# Project_Custom_Segmented_Display_2025-12.net
KiCad netlist of a schematic drawn in EasyEDA Pro
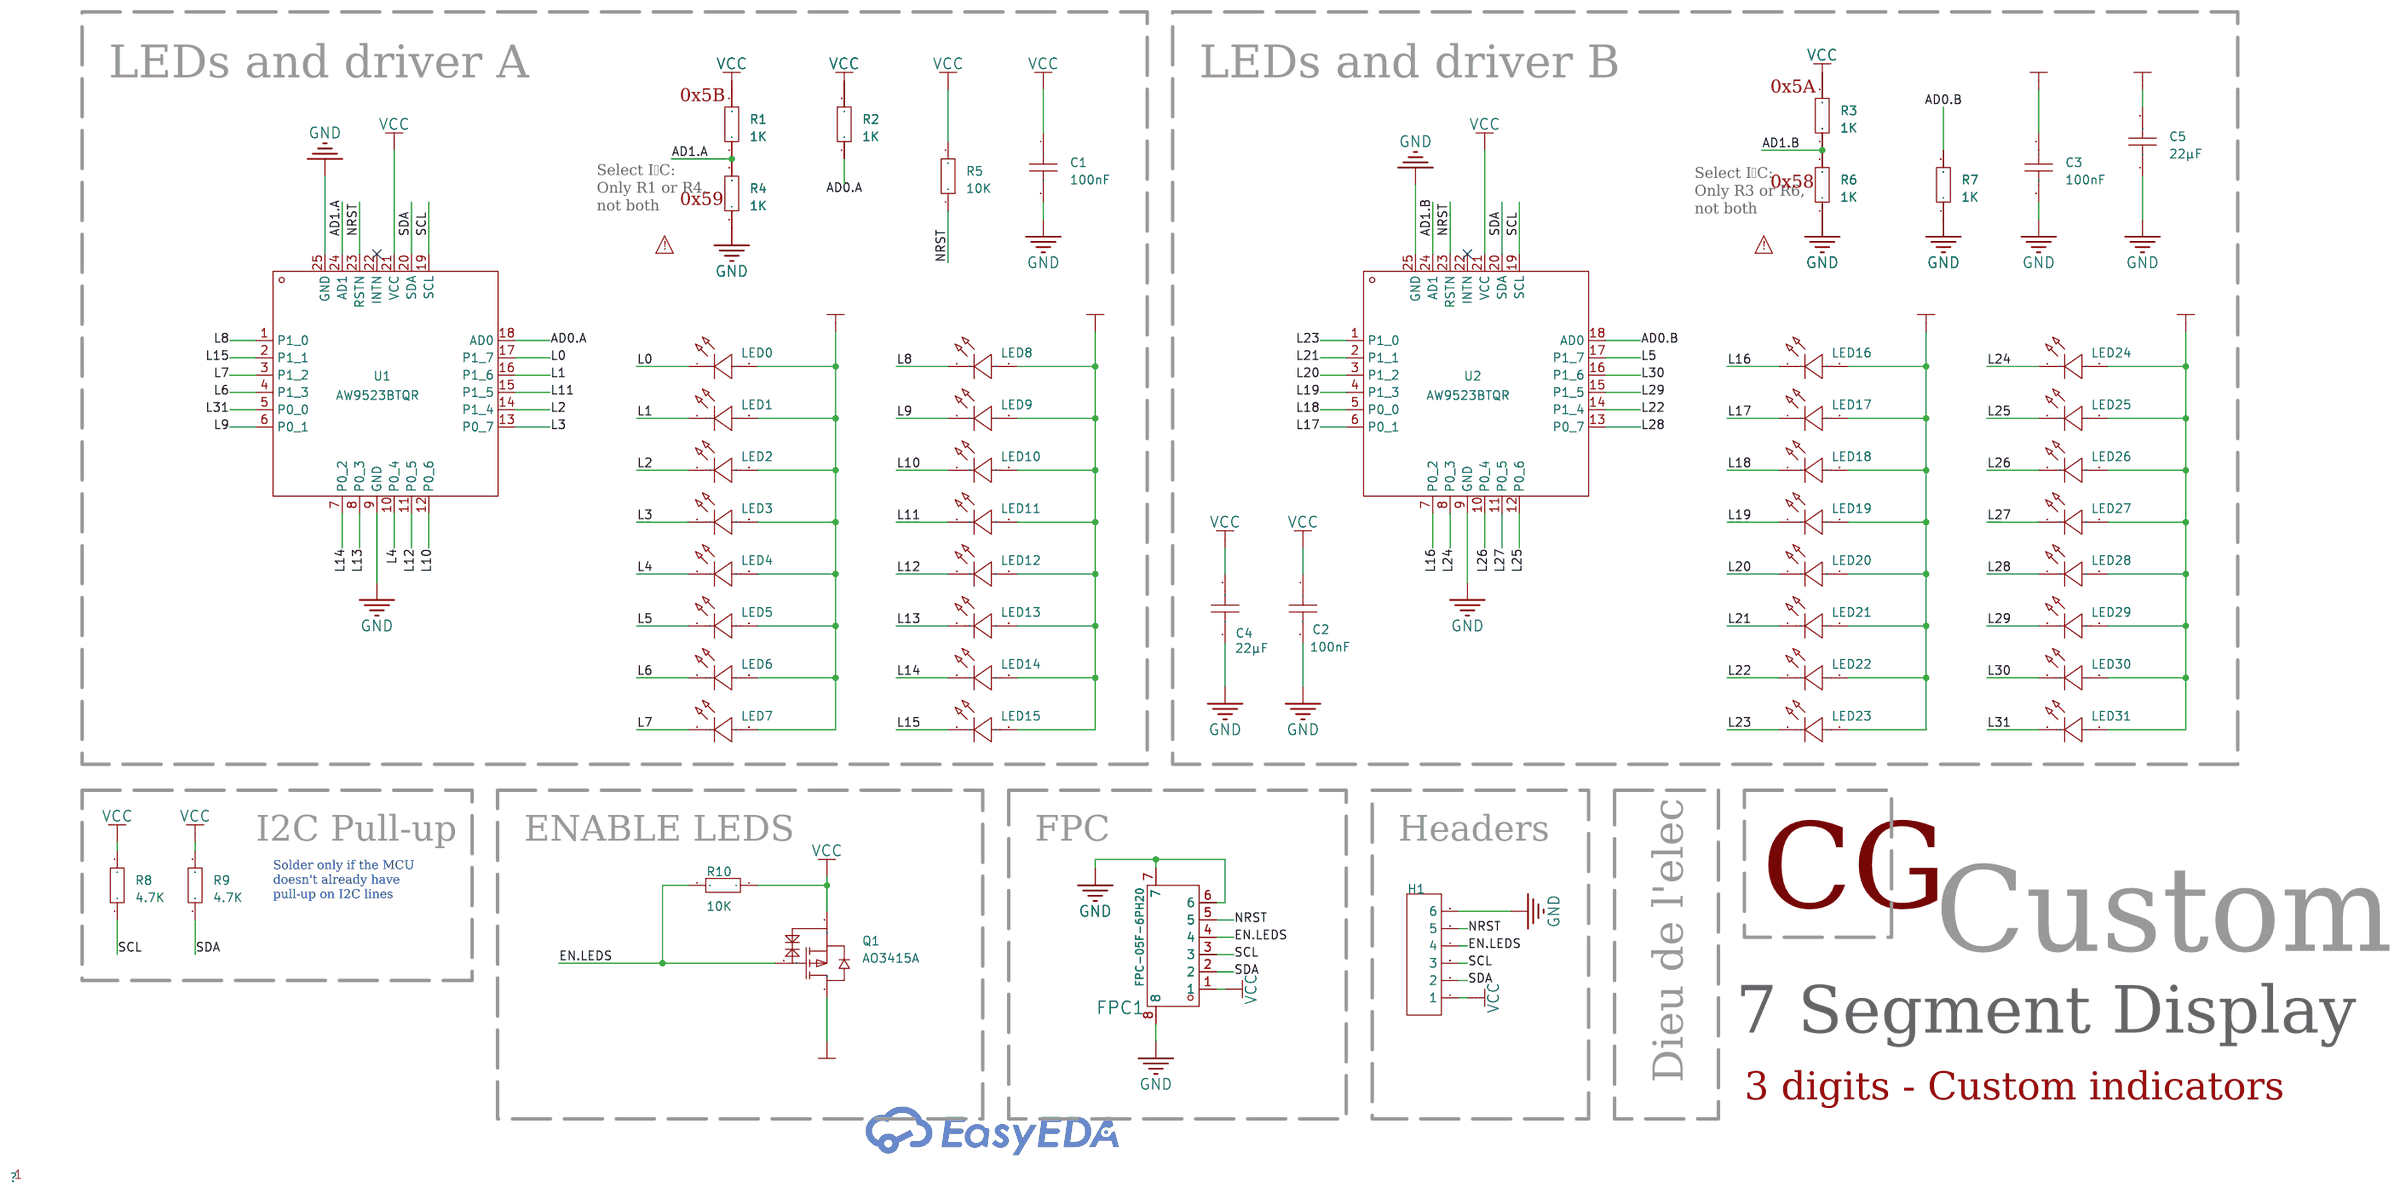
[diagram p0: schematic sheet]

(export (version "E")
  (design (tool "Eeschema 10.0.6"))
  (components
    (comp (ref "C1")
      (value "100nF")
      (footprint "easyedapro:C0805")
      (libsource (lib "easyedapro") (part "CAP"))
    )
    (comp (ref "C2")
      (value "100nF")
      (footprint "easyedapro:C0805")
      (libsource (lib "easyedapro") (part "CAP"))
    )
    (comp (ref "C3")
      (value "100nF")
      (footprint "easyedapro:C0805")
      (libsource (lib "easyedapro") (part "CAP"))
    )
    (comp (ref "C4")
      (value "22µF")
      (footprint "easyedapro:C0805")
      (libsource (lib "easyedapro") (part "CAP"))
    )
    (comp (ref "C5")
      (value "22µF")
      (footprint "easyedapro:C0805")
      (libsource (lib "easyedapro") (part "CAP"))
    )
    (comp (ref "FPC1")
      (value "FPC-05F-6PH20")
      (footprint "easyedapro:FPC-SMD_6P-P0.50_XUNPU_FPC-05F-6PH20")
      (fields (field (name "Manufacturer") "XUNPU(讯普)"))
      (libsource (lib "easyedapro") (part "FPC-05F-6PH20"))
    )
    (comp (ref "H1")
      (value "~")
      (footprint "easyedapro:HDR-TH_6P-P2.54-V-M-1")
      (libsource (lib "easyedapro") (part "Header-Male-2.54_1x6"))
    )
    (comp (ref "LED0")
      (value "XL-1608SURC-06")
      (footprint "easyedapro:LED0603-RD_RED")
      (fields (field (name "Manufacturer") "XINGLIGHT(成兴光)"))
      (libsource (lib "easyedapro") (part "XL-1608SURC-06"))
    )
    (comp (ref "LED1")
      (value "XL-1608SURC-06")
      (footprint "easyedapro:LED0603-RD_RED")
      (fields (field (name "Manufacturer") "XINGLIGHT(成兴光)"))
      (libsource (lib "easyedapro") (part "XL-1608SURC-06"))
    )
    (comp (ref "LED2")
      (value "XL-1608SURC-06")
      (footprint "easyedapro:LED0603-RD_RED")
      (fields (field (name "Manufacturer") "XINGLIGHT(成兴光)"))
      (libsource (lib "easyedapro") (part "XL-1608SURC-06"))
    )
    (comp (ref "LED3")
      (value "XL-1608SURC-06")
      (footprint "easyedapro:LED0603-RD_RED")
      (fields (field (name "Manufacturer") "XINGLIGHT(成兴光)"))
      (libsource (lib "easyedapro") (part "XL-1608SURC-06"))
    )
    (comp (ref "LED4")
      (value "XL-1608SURC-06")
      (footprint "easyedapro:LED0603-RD_RED")
      (fields (field (name "Manufacturer") "XINGLIGHT(成兴光)"))
      (libsource (lib "easyedapro") (part "XL-1608SURC-06"))
    )
    (comp (ref "LED5")
      (value "XL-1608SURC-06")
      (footprint "easyedapro:LED0603-RD_RED")
      (fields (field (name "Manufacturer") "XINGLIGHT(成兴光)"))
      (libsource (lib "easyedapro") (part "XL-1608SURC-06"))
    )
    (comp (ref "LED6")
      (value "XL-1608SURC-06")
      (footprint "easyedapro:LED0603-RD_RED")
      (fields (field (name "Manufacturer") "XINGLIGHT(成兴光)"))
      (libsource (lib "easyedapro") (part "XL-1608SURC-06"))
    )
    (comp (ref "LED7")
      (value "XL-1608SURC-06")
      (footprint "easyedapro:LED0603-RD_RED")
      (fields (field (name "Manufacturer") "XINGLIGHT(成兴光)"))
      (libsource (lib "easyedapro") (part "XL-1608SURC-06"))
    )
    (comp (ref "LED8")
      (value "XL-1608SURC-06")
      (footprint "easyedapro:LED0603-RD_RED")
      (fields (field (name "Manufacturer") "XINGLIGHT(成兴光)"))
      (libsource (lib "easyedapro") (part "XL-1608SURC-06"))
    )
    (comp (ref "LED9")
      (value "XL-1608SURC-06")
      (footprint "easyedapro:LED0603-RD_RED")
      (fields (field (name "Manufacturer") "XINGLIGHT(成兴光)"))
      (libsource (lib "easyedapro") (part "XL-1608SURC-06"))
    )
    (comp (ref "LED10")
      (value "XL-1608SURC-06")
      (footprint "easyedapro:LED0603-RD_RED")
      (fields (field (name "Manufacturer") "XINGLIGHT(成兴光)"))
      (libsource (lib "easyedapro") (part "XL-1608SURC-06"))
    )
    (comp (ref "LED11")
      (value "XL-1608SURC-06")
      (footprint "easyedapro:LED0603-RD_RED")
      (fields (field (name "Manufacturer") "XINGLIGHT(成兴光)"))
      (libsource (lib "easyedapro") (part "XL-1608SURC-06"))
    )
    (comp (ref "LED12")
      (value "XL-1608SURC-06")
      (footprint "easyedapro:LED0603-RD_RED")
      (fields (field (name "Manufacturer") "XINGLIGHT(成兴光)"))
      (libsource (lib "easyedapro") (part "XL-1608SURC-06"))
    )
    (comp (ref "LED13")
      (value "XL-1608SURC-06")
      (footprint "easyedapro:LED0603-RD_RED")
      (fields (field (name "Manufacturer") "XINGLIGHT(成兴光)"))
      (libsource (lib "easyedapro") (part "XL-1608SURC-06"))
    )
    (comp (ref "LED14")
      (value "XL-1608SURC-06")
      (footprint "easyedapro:LED0603-RD_RED")
      (fields (field (name "Manufacturer") "XINGLIGHT(成兴光)"))
      (libsource (lib "easyedapro") (part "XL-1608SURC-06"))
    )
    (comp (ref "LED15")
      (value "XL-1608SURC-06")
      (footprint "easyedapro:LED0603-RD_RED")
      (fields (field (name "Manufacturer") "XINGLIGHT(成兴光)"))
      (libsource (lib "easyedapro") (part "XL-1608SURC-06"))
    )
    (comp (ref "LED16")
      (value "XL-1608SURC-06")
      (footprint "easyedapro:LED0603-RD_RED")
      (fields (field (name "Manufacturer") "XINGLIGHT(成兴光)"))
      (libsource (lib "easyedapro") (part "XL-1608SURC-06"))
    )
    (comp (ref "LED17")
      (value "XL-1608SURC-06")
      (footprint "easyedapro:LED0603-RD_RED")
      (fields (field (name "Manufacturer") "XINGLIGHT(成兴光)"))
      (libsource (lib "easyedapro") (part "XL-1608SURC-06"))
    )
    (comp (ref "LED18")
      (value "XL-1608SURC-06")
      (footprint "easyedapro:LED0603-RD_RED")
      (fields (field (name "Manufacturer") "XINGLIGHT(成兴光)"))
      (libsource (lib "easyedapro") (part "XL-1608SURC-06"))
    )
    (comp (ref "LED19")
      (value "XL-1608SURC-06")
      (footprint "easyedapro:LED0603-RD_RED")
      (fields (field (name "Manufacturer") "XINGLIGHT(成兴光)"))
      (libsource (lib "easyedapro") (part "XL-1608SURC-06"))
    )
    (comp (ref "LED20")
      (value "XL-1608SURC-06")
      (footprint "easyedapro:LED0603-RD_RED")
      (fields (field (name "Manufacturer") "XINGLIGHT(成兴光)"))
      (libsource (lib "easyedapro") (part "XL-1608SURC-06"))
    )
    (comp (ref "LED21")
      (value "XL-1608SURC-06")
      (footprint "easyedapro:LED0603-RD_RED")
      (fields (field (name "Manufacturer") "XINGLIGHT(成兴光)"))
      (libsource (lib "easyedapro") (part "XL-1608SURC-06"))
    )
    (comp (ref "LED22")
      (value "XL-1608SURC-06")
      (footprint "easyedapro:LED0603-RD_RED")
      (fields (field (name "Manufacturer") "XINGLIGHT(成兴光)"))
      (libsource (lib "easyedapro") (part "XL-1608SURC-06"))
    )
    (comp (ref "LED23")
      (value "XL-1608SURC-06")
      (footprint "easyedapro:LED0603-RD_RED")
      (fields (field (name "Manufacturer") "XINGLIGHT(成兴光)"))
      (libsource (lib "easyedapro") (part "XL-1608SURC-06"))
    )
    (comp (ref "LED24")
      (value "XL-1608SURC-06")
      (footprint "easyedapro:LED0603-RD_RED")
      (fields (field (name "Manufacturer") "XINGLIGHT(成兴光)"))
      (libsource (lib "easyedapro") (part "XL-1608SURC-06"))
    )
    (comp (ref "LED25")
      (value "XL-1608SURC-06")
      (footprint "easyedapro:LED0603-RD_RED")
      (fields (field (name "Manufacturer") "XINGLIGHT(成兴光)"))
      (libsource (lib "easyedapro") (part "XL-1608SURC-06"))
    )
    (comp (ref "LED26")
      (value "XL-1608SURC-06")
      (footprint "easyedapro:LED0603-RD_RED")
      (fields (field (name "Manufacturer") "XINGLIGHT(成兴光)"))
      (libsource (lib "easyedapro") (part "XL-1608SURC-06"))
    )
    (comp (ref "LED27")
      (value "XL-1608SURC-06")
      (footprint "easyedapro:LED0603-RD_RED")
      (fields (field (name "Manufacturer") "XINGLIGHT(成兴光)"))
      (libsource (lib "easyedapro") (part "XL-1608SURC-06"))
    )
    (comp (ref "LED28")
      (value "XL-1608SURC-06")
      (footprint "easyedapro:LED0603-RD_RED")
      (fields (field (name "Manufacturer") "XINGLIGHT(成兴光)"))
      (libsource (lib "easyedapro") (part "XL-1608SURC-06"))
    )
    (comp (ref "LED29")
      (value "XL-1608SURC-06")
      (footprint "easyedapro:LED0603-RD_RED")
      (fields (field (name "Manufacturer") "XINGLIGHT(成兴光)"))
      (libsource (lib "easyedapro") (part "XL-1608SURC-06"))
    )
    (comp (ref "LED30")
      (value "XL-1608SURC-06")
      (footprint "easyedapro:LED0603-RD_RED")
      (fields (field (name "Manufacturer") "XINGLIGHT(成兴光)"))
      (libsource (lib "easyedapro") (part "XL-1608SURC-06"))
    )
    (comp (ref "LED31")
      (value "XL-1608SURC-06")
      (footprint "easyedapro:LED0603-RD_RED")
      (fields (field (name "Manufacturer") "XINGLIGHT(成兴光)"))
      (libsource (lib "easyedapro") (part "XL-1608SURC-06"))
    )
    (comp (ref "Q1")
      (value "AO3415A")
      (footprint "easyedapro:SOT-23-3_L2.9-W1.6-P1.90-LS2.8-BR")
      (fields (field (name "Manufacturer") "AOS"))
      (libsource (lib "easyedapro") (part "AO3415A"))
    )
    (comp (ref "R1") (value "1K") (footprint "easyedapro:R0603") (libsource (lib "easyedapro") (part "Res")))
    (comp (ref "R2") (value "1K") (footprint "easyedapro:R0603") (libsource (lib "easyedapro") (part "Res")))
    (comp (ref "R3") (value "1K") (footprint "easyedapro:R0603") (libsource (lib "easyedapro") (part "Res")))
    (comp (ref "R4") (value "1K") (footprint "easyedapro:R0603") (libsource (lib "easyedapro") (part "Res")))
    (comp (ref "R5") (value "10K") (footprint "easyedapro:R0603") (libsource (lib "easyedapro") (part "Res")))
    (comp (ref "R6") (value "1K") (footprint "easyedapro:R0603") (libsource (lib "easyedapro") (part "Res")))
    (comp (ref "R7") (value "1K") (footprint "easyedapro:R0603") (libsource (lib "easyedapro") (part "Res")))
    (comp (ref "R8")
      (value "4.7K")
      (footprint "easyedapro:R0603")
      (libsource (lib "easyedapro") (part "Res"))
    )
    (comp (ref "R9")
      (value "4.7K")
      (footprint "easyedapro:R0603")
      (libsource (lib "easyedapro") (part "Res"))
    )
    (comp (ref "R10")
      (value "10K")
      (footprint "easyedapro:R0603")
      (libsource (lib "easyedapro") (part "Res"))
    )
    (comp (ref "U1")
      (value "AW9523BTQR")
      (footprint "easyedapro:VFQFPN-24_L4.0-W4.0-P0.50-BL-EP2.8")
      (fields (field (name "Manufacturer") "AWINIC(艾为)"))
      (libsource (lib "easyedapro") (part "AW9523BTQR"))
    )
    (comp (ref "U2")
      (value "AW9523BTQR")
      (footprint "easyedapro:VFQFPN-24_L4.0-W4.0-P0.50-BL-EP2.8")
      (fields (field (name "Manufacturer") "AWINIC(艾为)"))
      (libsource (lib "easyedapro") (part "AW9523BTQR"))
    )
  )
  (nets
    (net (code "1") (name "/AD0.A") (class "Default")
      (node (ref "R2") (pin "1") (pinfunction "1_1") (pintype "input"))
      (node (ref "U1") (pin "18") (pinfunction "AD0_18") (pintype "unspecified"))
    )
    (net (code "2") (name "/AD0.B") (class "Default")
      (node (ref "R7") (pin "2") (pinfunction "2_2") (pintype "input"))
      (node (ref "U2") (pin "18") (pinfunction "AD0_18") (pintype "unspecified"))
    )
    (net (code "3") (name "/AD1.A") (class "Default")
      (node (ref "R1") (pin "1") (pinfunction "1_1") (pintype "input"))
      (node (ref "R4") (pin "2") (pinfunction "2_2") (pintype "input"))
      (node (ref "U1") (pin "24") (pinfunction "AD1_24") (pintype "unspecified"))
    )
    (net (code "4") (name "/AD1.B") (class "Default")
      (node (ref "R3") (pin "1") (pinfunction "1_1") (pintype "input"))
      (node (ref "R6") (pin "2") (pinfunction "2_2") (pintype "input"))
      (node (ref "U2") (pin "24") (pinfunction "AD1_24") (pintype "unspecified"))
    )
    (net (code "5") (name "/EN.LEDS") (class "Default")
      (node (ref "FPC1") (pin "4") (pinfunction "4_4") (pintype "input"))
      (node (ref "H1") (pin "4") (pinfunction "4_4") (pintype "input"))
      (node (ref "Q1") (pin "1") (pinfunction "G_1") (pintype "unspecified"))
      (node (ref "R10") (pin "2") (pinfunction "2_2") (pintype "input"))
    )
    (net (code "6") (name "/L0") (class "Default")
      (node (ref "LED0") (pin "1") (pinfunction "K_1") (pintype "unspecified"))
      (node (ref "U1") (pin "17") (pinfunction "P1_7_17") (pintype "unspecified"))
    )
    (net (code "7") (name "/L1") (class "Default")
      (node (ref "LED1") (pin "1") (pinfunction "K_1") (pintype "unspecified"))
      (node (ref "U1") (pin "16") (pinfunction "P1_6_16") (pintype "unspecified"))
    )
    (net (code "8") (name "/L2") (class "Default")
      (node (ref "LED2") (pin "1") (pinfunction "K_1") (pintype "unspecified"))
      (node (ref "U1") (pin "14") (pinfunction "P1_4_14") (pintype "unspecified"))
    )
    (net (code "9") (name "/L3") (class "Default")
      (node (ref "LED3") (pin "1") (pinfunction "K_1") (pintype "unspecified"))
      (node (ref "U1") (pin "13") (pinfunction "P0_7_13") (pintype "unspecified"))
    )
    (net (code "10") (name "/L4") (class "Default")
      (node (ref "LED4") (pin "1") (pinfunction "K_1") (pintype "unspecified"))
      (node (ref "U1") (pin "10") (pinfunction "P0_4_10") (pintype "unspecified"))
    )
    (net (code "11") (name "/L5") (class "Default")
      (node (ref "LED5") (pin "1") (pinfunction "K_1") (pintype "unspecified"))
      (node (ref "U2") (pin "17") (pinfunction "P1_7_17") (pintype "unspecified"))
    )
    (net (code "12") (name "/L6") (class "Default")
      (node (ref "LED6") (pin "1") (pinfunction "K_1") (pintype "unspecified"))
      (node (ref "U1") (pin "4") (pinfunction "P1_3_4") (pintype "unspecified"))
    )
    (net (code "13") (name "/L7") (class "Default")
      (node (ref "LED7") (pin "1") (pinfunction "K_1") (pintype "unspecified"))
      (node (ref "U1") (pin "3") (pinfunction "P1_2_3") (pintype "unspecified"))
    )
    (net (code "14") (name "/L8") (class "Default")
      (node (ref "LED8") (pin "1") (pinfunction "K_1") (pintype "unspecified"))
      (node (ref "U1") (pin "1") (pinfunction "P1_0_1") (pintype "unspecified"))
    )
    (net (code "15") (name "/L9") (class "Default")
      (node (ref "LED9") (pin "1") (pinfunction "K_1") (pintype "unspecified"))
      (node (ref "U1") (pin "6") (pinfunction "P0_1_6") (pintype "unspecified"))
    )
    (net (code "16") (name "/L10") (class "Default")
      (node (ref "LED10") (pin "1") (pinfunction "K_1") (pintype "unspecified"))
      (node (ref "U1") (pin "12") (pinfunction "P0_6_12") (pintype "unspecified"))
    )
    (net (code "17") (name "/L11") (class "Default")
      (node (ref "LED11") (pin "1") (pinfunction "K_1") (pintype "unspecified"))
      (node (ref "U1") (pin "15") (pinfunction "P1_5_15") (pintype "unspecified"))
    )
    (net (code "18") (name "/L12") (class "Default")
      (node (ref "LED12") (pin "1") (pinfunction "K_1") (pintype "unspecified"))
      (node (ref "U1") (pin "11") (pinfunction "P0_5_11") (pintype "unspecified"))
    )
    (net (code "19") (name "/L13") (class "Default")
      (node (ref "LED13") (pin "1") (pinfunction "K_1") (pintype "unspecified"))
      (node (ref "U1") (pin "8") (pinfunction "P0_3_8") (pintype "unspecified"))
    )
    (net (code "20") (name "/L14") (class "Default")
      (node (ref "LED14") (pin "1") (pinfunction "K_1") (pintype "unspecified"))
      (node (ref "U1") (pin "7") (pinfunction "P0_2_7") (pintype "unspecified"))
    )
    (net (code "21") (name "/L15") (class "Default")
      (node (ref "LED15") (pin "1") (pinfunction "K_1") (pintype "unspecified"))
      (node (ref "U1") (pin "2") (pinfunction "P1_1_2") (pintype "unspecified"))
    )
    (net (code "22") (name "/L16") (class "Default")
      (node (ref "LED16") (pin "1") (pinfunction "K_1") (pintype "unspecified"))
      (node (ref "U2") (pin "7") (pinfunction "P0_2_7") (pintype "unspecified"))
    )
    (net (code "23") (name "/L17") (class "Default")
      (node (ref "LED17") (pin "1") (pinfunction "K_1") (pintype "unspecified"))
      (node (ref "U2") (pin "6") (pinfunction "P0_1_6") (pintype "unspecified"))
    )
    (net (code "24") (name "/L18") (class "Default")
      (node (ref "LED18") (pin "1") (pinfunction "K_1") (pintype "unspecified"))
      (node (ref "U2") (pin "5") (pinfunction "P0_0_5") (pintype "unspecified"))
    )
    (net (code "25") (name "/L19") (class "Default")
      (node (ref "LED19") (pin "1") (pinfunction "K_1") (pintype "unspecified"))
      (node (ref "U2") (pin "4") (pinfunction "P1_3_4") (pintype "unspecified"))
    )
    (net (code "26") (name "/L20") (class "Default")
      (node (ref "LED20") (pin "1") (pinfunction "K_1") (pintype "unspecified"))
      (node (ref "U2") (pin "3") (pinfunction "P1_2_3") (pintype "unspecified"))
    )
    (net (code "27") (name "/L21") (class "Default")
      (node (ref "LED21") (pin "1") (pinfunction "K_1") (pintype "unspecified"))
      (node (ref "U2") (pin "2") (pinfunction "P1_1_2") (pintype "unspecified"))
    )
    (net (code "28") (name "/L22") (class "Default")
      (node (ref "LED22") (pin "1") (pinfunction "K_1") (pintype "unspecified"))
      (node (ref "U2") (pin "14") (pinfunction "P1_4_14") (pintype "unspecified"))
    )
    (net (code "29") (name "/L23") (class "Default")
      (node (ref "LED23") (pin "1") (pinfunction "K_1") (pintype "unspecified"))
      (node (ref "U2") (pin "1") (pinfunction "P1_0_1") (pintype "unspecified"))
    )
    (net (code "30") (name "/L24") (class "Default")
      (node (ref "LED24") (pin "1") (pinfunction "K_1") (pintype "unspecified"))
      (node (ref "U2") (pin "8") (pinfunction "P0_3_8") (pintype "unspecified"))
    )
    (net (code "31") (name "/L25") (class "Default")
      (node (ref "LED25") (pin "1") (pinfunction "K_1") (pintype "unspecified"))
      (node (ref "U2") (pin "12") (pinfunction "P0_6_12") (pintype "unspecified"))
    )
    (net (code "32") (name "/L26") (class "Default")
      (node (ref "LED26") (pin "1") (pinfunction "K_1") (pintype "unspecified"))
      (node (ref "U2") (pin "10") (pinfunction "P0_4_10") (pintype "unspecified"))
    )
    (net (code "33") (name "/L27") (class "Default")
      (node (ref "LED27") (pin "1") (pinfunction "K_1") (pintype "unspecified"))
      (node (ref "U2") (pin "11") (pinfunction "P0_5_11") (pintype "unspecified"))
    )
    (net (code "34") (name "/L28") (class "Default")
      (node (ref "LED28") (pin "1") (pinfunction "K_1") (pintype "unspecified"))
      (node (ref "U2") (pin "13") (pinfunction "P0_7_13") (pintype "unspecified"))
    )
    (net (code "35") (name "/L29") (class "Default")
      (node (ref "LED29") (pin "1") (pinfunction "K_1") (pintype "unspecified"))
      (node (ref "U2") (pin "15") (pinfunction "P1_5_15") (pintype "unspecified"))
    )
    (net (code "36") (name "/L30") (class "Default")
      (node (ref "LED30") (pin "1") (pinfunction "K_1") (pintype "unspecified"))
      (node (ref "U2") (pin "16") (pinfunction "P1_6_16") (pintype "unspecified"))
    )
    (net (code "37") (name "/L31") (class "Default")
      (node (ref "LED31") (pin "1") (pinfunction "K_1") (pintype "unspecified"))
      (node (ref "U1") (pin "5") (pinfunction "P0_0_5") (pintype "unspecified"))
    )
    (net (code "38") (name "/NRST") (class "Default")
      (node (ref "FPC1") (pin "5") (pinfunction "5_5") (pintype "input"))
      (node (ref "H1") (pin "5") (pinfunction "5_5") (pintype "input"))
      (node (ref "R5") (pin "1") (pinfunction "1_1") (pintype "input"))
      (node (ref "U1") (pin "23") (pinfunction "RSTN_23") (pintype "unspecified"))
      (node (ref "U2") (pin "23") (pinfunction "RSTN_23") (pintype "unspecified"))
    )
    (net (code "39") (name "/SCL") (class "Default")
      (node (ref "FPC1") (pin "3") (pinfunction "3_3") (pintype "input"))
      (node (ref "H1") (pin "3") (pinfunction "3_3") (pintype "input"))
      (node (ref "R8") (pin "1") (pinfunction "1_1") (pintype "input"))
      (node (ref "U1") (pin "19") (pinfunction "SCL_19") (pintype "unspecified"))
      (node (ref "U2") (pin "19") (pinfunction "SCL_19") (pintype "unspecified"))
    )
    (net (code "40") (name "/SDA") (class "Default")
      (node (ref "FPC1") (pin "2") (pinfunction "2_2") (pintype "input"))
      (node (ref "H1") (pin "2") (pinfunction "2_2") (pintype "input"))
      (node (ref "R9") (pin "1") (pinfunction "1_1") (pintype "input"))
      (node (ref "U1") (pin "20") (pinfunction "SDA_20") (pintype "unspecified"))
      (node (ref "U2") (pin "20") (pinfunction "SDA_20") (pintype "unspecified"))
    )
    (net (code "41") (name "GND") (class "Default")
      (node (ref "C1") (pin "2") (pinfunction "2_2") (pintype "input"))
      (node (ref "C2") (pin "2") (pinfunction "2_2") (pintype "input"))
      (node (ref "C3") (pin "2") (pinfunction "2_2") (pintype "input"))
      (node (ref "C4") (pin "1") (pinfunction "1_1") (pintype "input"))
      (node (ref "C5") (pin "1") (pinfunction "1_1") (pintype "input"))
      (node (ref "FPC1") (pin "6") (pinfunction "6_6") (pintype "input"))
      (node (ref "FPC1") (pin "7") (pinfunction "7_7") (pintype "input"))
      (node (ref "FPC1") (pin "8") (pinfunction "8_8") (pintype "input"))
      (node (ref "H1") (pin "6") (pinfunction "6_6") (pintype "input"))
      (node (ref "R4") (pin "1") (pinfunction "1_1") (pintype "input"))
      (node (ref "R6") (pin "1") (pinfunction "1_1") (pintype "input"))
      (node (ref "R7") (pin "1") (pinfunction "1_1") (pintype "input"))
      (node (ref "U1") (pin "25") (pinfunction "GND_25") (pintype "unspecified"))
      (node (ref "U1") (pin "9") (pinfunction "GND_9") (pintype "unspecified"))
      (node (ref "U2") (pin "25") (pinfunction "GND_25") (pintype "unspecified"))
      (node (ref "U2") (pin "9") (pinfunction "GND_9") (pintype "unspecified"))
    )
    (net (code "42") (name "VCC") (class "Default")
      (node (ref "C1") (pin "1") (pinfunction "1_1") (pintype "input"))
      (node (ref "C2") (pin "1") (pinfunction "1_1") (pintype "input"))
      (node (ref "C4") (pin "2") (pinfunction "2_2") (pintype "input"))
      (node (ref "FPC1") (pin "1") (pinfunction "1_1") (pintype "input"))
      (node (ref "H1") (pin "1") (pinfunction "1_1") (pintype "input"))
      (node (ref "Q1") (pin "2") (pinfunction "S_2") (pintype "unspecified"))
      (node (ref "R1") (pin "2") (pinfunction "2_2") (pintype "input"))
      (node (ref "R10") (pin "1") (pinfunction "1_1") (pintype "input"))
      (node (ref "R2") (pin "2") (pinfunction "2_2") (pintype "input"))
      (node (ref "R3") (pin "2") (pinfunction "2_2") (pintype "input"))
      (node (ref "R5") (pin "2") (pinfunction "2_2") (pintype "input"))
      (node (ref "R8") (pin "2") (pinfunction "2_2") (pintype "input"))
      (node (ref "R9") (pin "2") (pinfunction "2_2") (pintype "input"))
      (node (ref "U1") (pin "21") (pinfunction "VCC_21") (pintype "unspecified"))
      (node (ref "U2") (pin "21") (pinfunction "VCC_21") (pintype "unspecified"))
    )
    (net (code "43") (name "VCC.LED") (class "Default")
      (node (ref "C3") (pin "1") (pinfunction "1_1") (pintype "input"))
      (node (ref "C5") (pin "2") (pinfunction "2_2") (pintype "input"))
      (node (ref "LED0") (pin "2") (pinfunction "A_2") (pintype "unspecified"))
      (node (ref "LED1") (pin "2") (pinfunction "A_2") (pintype "unspecified"))
      (node (ref "LED10") (pin "2") (pinfunction "A_2") (pintype "unspecified"))
      (node (ref "LED11") (pin "2") (pinfunction "A_2") (pintype "unspecified"))
      (node (ref "LED12") (pin "2") (pinfunction "A_2") (pintype "unspecified"))
      (node (ref "LED13") (pin "2") (pinfunction "A_2") (pintype "unspecified"))
      (node (ref "LED14") (pin "2") (pinfunction "A_2") (pintype "unspecified"))
      (node (ref "LED15") (pin "2") (pinfunction "A_2") (pintype "unspecified"))
      (node (ref "LED16") (pin "2") (pinfunction "A_2") (pintype "unspecified"))
      (node (ref "LED17") (pin "2") (pinfunction "A_2") (pintype "unspecified"))
      (node (ref "LED18") (pin "2") (pinfunction "A_2") (pintype "unspecified"))
      (node (ref "LED19") (pin "2") (pinfunction "A_2") (pintype "unspecified"))
      (node (ref "LED2") (pin "2") (pinfunction "A_2") (pintype "unspecified"))
      (node (ref "LED20") (pin "2") (pinfunction "A_2") (pintype "unspecified"))
      (node (ref "LED21") (pin "2") (pinfunction "A_2") (pintype "unspecified"))
      (node (ref "LED22") (pin "2") (pinfunction "A_2") (pintype "unspecified"))
      (node (ref "LED23") (pin "2") (pinfunction "A_2") (pintype "unspecified"))
      (node (ref "LED24") (pin "2") (pinfunction "A_2") (pintype "unspecified"))
      (node (ref "LED25") (pin "2") (pinfunction "A_2") (pintype "unspecified"))
      (node (ref "LED26") (pin "2") (pinfunction "A_2") (pintype "unspecified"))
      (node (ref "LED27") (pin "2") (pinfunction "A_2") (pintype "unspecified"))
      (node (ref "LED28") (pin "2") (pinfunction "A_2") (pintype "unspecified"))
      (node (ref "LED29") (pin "2") (pinfunction "A_2") (pintype "unspecified"))
      (node (ref "LED3") (pin "2") (pinfunction "A_2") (pintype "unspecified"))
      (node (ref "LED30") (pin "2") (pinfunction "A_2") (pintype "unspecified"))
      (node (ref "LED31") (pin "2") (pinfunction "A_2") (pintype "unspecified"))
      (node (ref "LED4") (pin "2") (pinfunction "A_2") (pintype "unspecified"))
      (node (ref "LED5") (pin "2") (pinfunction "A_2") (pintype "unspecified"))
      (node (ref "LED6") (pin "2") (pinfunction "A_2") (pintype "unspecified"))
      (node (ref "LED7") (pin "2") (pinfunction "A_2") (pintype "unspecified"))
      (node (ref "LED8") (pin "2") (pinfunction "A_2") (pintype "unspecified"))
      (node (ref "LED9") (pin "2") (pinfunction "A_2") (pintype "unspecified"))
      (node (ref "Q1") (pin "3") (pinfunction "D_3") (pintype "unspecified"))
    )
    (net (code "44") (name "unconnected-(U1-INTN-Pad22)") (class "Default")
      (node (ref "U1") (pin "22") (pinfunction "INTN_22") (pintype "unspecified+no_connect"))
    )
    (net (code "45") (name "unconnected-(U2-INTN-Pad22)") (class "Default")
      (node (ref "U2") (pin "22") (pinfunction "INTN_22") (pintype "unspecified+no_connect"))
    )
  )
)
